# MTP10.net
KiCad netlist of a schematic drawn in Altium Designer
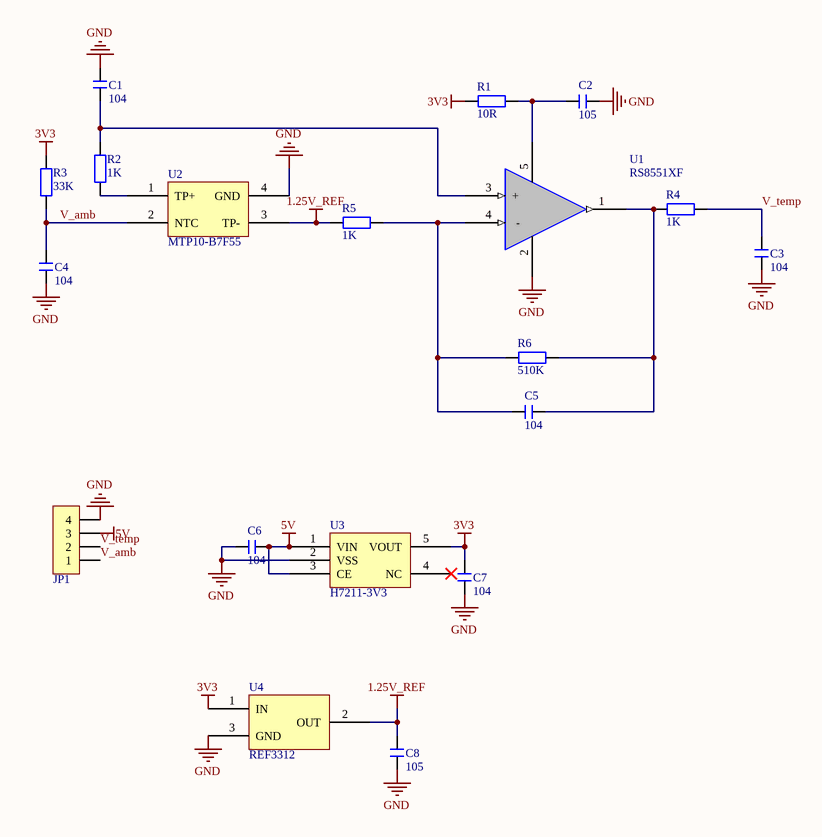
[diagram p0: MTP10.SchDoc]

(export (version "E")
  (design (tool "Eeschema 10.0.6"))
  (components
    (comp (ref "C1")
      (value "104")
      (footprint "C 0603_L")
      (description "无极性贴片电容")
      (fields (field (name "版权归属") "源创客"))
      (libsource (lib "3.1   - 电阻-电容-电感") (part "C"))
    )
    (comp (ref "C2")
      (value "105")
      (footprint "C 0603_L")
      (description "无极性贴片电容")
      (fields (field (name "版权归属") "源创客"))
      (libsource (lib "3.1   - 电阻-电容-电感") (part "C"))
    )
    (comp (ref "C3")
      (value "104")
      (footprint "C 0603_L")
      (description "无极性贴片电容")
      (fields (field (name "版权归属") "源创客"))
      (libsource (lib "3.1   - 电阻-电容-电感") (part "C"))
    )
    (comp (ref "C4")
      (value "104")
      (footprint "C 0603_L")
      (description "无极性贴片电容")
      (fields (field (name "版权归属") "源创客"))
      (libsource (lib "3.1   - 电阻-电容-电感") (part "C"))
    )
    (comp (ref "C5")
      (value "104")
      (footprint "C 0603_L")
      (description "无极性贴片电容")
      (fields (field (name "版权归属") "源创客"))
      (libsource (lib "3.1   - 电阻-电容-电感") (part "C"))
    )
    (comp (ref "C6")
      (value "104")
      (footprint "C 0603_L")
      (description "无极性贴片电容")
      (fields (field (name "版权归属") "源创客"))
      (libsource (lib "3.1   - 电阻-电容-电感") (part "C"))
    )
    (comp (ref "C7")
      (value "104")
      (footprint "C 0603_L")
      (description "无极性贴片电容")
      (fields (field (name "版权归属") "源创客"))
      (libsource (lib "3.1   - 电阻-电容-电感") (part "C"))
    )
    (comp (ref "C8")
      (value "105")
      (footprint "C 0603_L")
      (description "无极性贴片电容")
      (fields (field (name "版权归属") "源创客"))
      (libsource (lib "3.1   - 电阻-电容-电感") (part "C"))
    )
    (comp (ref "JP1")
      (value "HDR-1X4")
      (footprint "HDR2.54-LI-4P")
      (description "4P接插件")
      (fields (field (name "版权归属") "源创客"))
      (libsource (lib "4.5   - 接插件-脚距2.54") (part "Header 4"))
    )
    (comp (ref "R1")
      (value "10R")
      (footprint "R 0603_L")
      (description "贴片电阻")
      (fields (field (name "版权归属") "源创客"))
      (libsource (lib "3.1   - 电阻-电容-电感") (part "R"))
    )
    (comp (ref "R2")
      (value "1K")
      (footprint "R 0603_L")
      (description "贴片电阻")
      (fields (field (name "版权归属") "源创客"))
      (libsource (lib "3.1   - 电阻-电容-电感") (part "R"))
    )
    (comp (ref "R3")
      (value "33K")
      (footprint "R 0603_L")
      (description "贴片电阻")
      (fields (field (name "版权归属") "源创客"))
      (libsource (lib "3.1   - 电阻-电容-电感") (part "R"))
    )
    (comp (ref "R4")
      (value "1K")
      (footprint "R 0603_L")
      (description "贴片电阻")
      (fields (field (name "版权归属") "源创客"))
      (libsource (lib "3.1   - 电阻-电容-电感") (part "R"))
    )
    (comp (ref "R5")
      (value "1K")
      (footprint "R 0603_L")
      (description "贴片电阻")
      (fields (field (name "版权归属") "源创客"))
      (libsource (lib "3.1   - 电阻-电容-电感") (part "R"))
    )
    (comp (ref "R6")
      (value "510K")
      (footprint "R 0603_L")
      (description "贴片电阻")
      (fields (field (name "版权归属") "源创客"))
      (libsource (lib "3.1   - 电阻-电容-电感") (part "R"))
    )
    (comp (ref "U1")
      (value "RS8551XF")
      (footprint "SOT23-5M")
      (description "仪表放大器")
      (libsource (lib "MTP10") (part "RS8551XF"))
    )
    (comp (ref "U2")
      (value "MTP10-B7F55")
      (footprint "MTP-10B")
      (description "MEMS 热电堆芯片")
      (libsource (lib "MTP10") (part "MTP10-B7F55"))
    )
    (comp (ref "U3")
      (value "H7211-3V3")
      (footprint "SOT23-5")
      (description "低噪声LDO")
      (libsource (lib "LMT70") (part "H7211"))
    )
    (comp (ref "U4")
      (value "REF3312")
      (footprint "SOT23-3L")
      (description "电压基准")
      (libsource (lib "MTP10") (part "REF33XX"))
    )
  )
  (nets
    (net (code "1") (name "/V_amb") (class "Default")
      (node (ref "C4") (pin "2") (pinfunction "2_2") (pintype "passive"))
      (node (ref "JP1") (pin "1") (pinfunction "1_1") (pintype "passive"))
      (node (ref "R3") (pin "1") (pinfunction "1_1") (pintype "passive"))
      (node (ref "U2") (pin "2") (pinfunction "NTC_2") (pintype "passive"))
    )
    (net (code "2") (name "/V_temp") (class "Default")
      (node (ref "C3") (pin "2") (pinfunction "2_2") (pintype "passive"))
      (node (ref "JP1") (pin "2") (pinfunction "2_2") (pintype "passive"))
      (node (ref "R4") (pin "1") (pinfunction "1_1") (pintype "passive"))
    )
    (net (code "3") (name "1.25V_REF") (class "Default")
      (node (ref "C8") (pin "2") (pinfunction "2_2") (pintype "passive"))
      (node (ref "R5") (pin "2") (pinfunction "2_2") (pintype "passive"))
      (node (ref "U2") (pin "3") (pinfunction "TP-_3") (pintype "passive"))
      (node (ref "U4") (pin "2") (pinfunction "OUT_2") (pintype "passive"))
    )
    (net (code "4") (name "3V3") (class "Default")
      (node (ref "C7") (pin "2") (pinfunction "2_2") (pintype "passive"))
      (node (ref "R1") (pin "2") (pinfunction "2_2") (pintype "passive"))
      (node (ref "R3") (pin "2") (pinfunction "2_2") (pintype "passive"))
      (node (ref "U3") (pin "5") (pinfunction "VOUT_5") (pintype "passive"))
      (node (ref "U4") (pin "1") (pinfunction "IN_1") (pintype "passive"))
    )
    (net (code "5") (name "5V") (class "Default")
      (node (ref "C6") (pin "1") (pinfunction "1_1") (pintype "passive"))
      (node (ref "JP1") (pin "3") (pinfunction "3_3") (pintype "passive"))
      (node (ref "U3") (pin "1") (pinfunction "VIN_1") (pintype "passive"))
      (node (ref "U3") (pin "3") (pinfunction "CE_3") (pintype "passive"))
    )
    (net (code "6") (name "GND") (class "Default")
      (node (ref "C1") (pin "1") (pinfunction "1_1") (pintype "passive"))
      (node (ref "C2") (pin "2") (pinfunction "2_2") (pintype "passive"))
      (node (ref "C3") (pin "1") (pinfunction "1_1") (pintype "passive"))
      (node (ref "C4") (pin "1") (pinfunction "1_1") (pintype "passive"))
      (node (ref "C6") (pin "2") (pinfunction "2_2") (pintype "passive"))
      (node (ref "C7") (pin "1") (pinfunction "1_1") (pintype "passive"))
      (node (ref "C8") (pin "1") (pinfunction "1_1") (pintype "passive"))
      (node (ref "JP1") (pin "4") (pinfunction "4_4") (pintype "passive"))
      (node (ref "U1") (pin "2") (pinfunction "GND_2") (pintype "power_in"))
      (node (ref "U2") (pin "4") (pinfunction "GND_4") (pintype "passive"))
      (node (ref "U3") (pin "2") (pinfunction "VSS_2") (pintype "passive"))
      (node (ref "U4") (pin "3") (pinfunction "GND_3") (pintype "passive"))
    )
    (net (code "7") (name "Net-(U1-+)") (class "Default")
      (node (ref "C1") (pin "2") (pinfunction "2_2") (pintype "passive"))
      (node (ref "R2") (pin "2") (pinfunction "2_2") (pintype "passive"))
      (node (ref "U1") (pin "3") (pinfunction "+_3") (pintype "input"))
    )
    (net (code "8") (name "Net-(U1-OUT)") (class "Default")
      (node (ref "C5") (pin "2") (pinfunction "2_2") (pintype "passive"))
      (node (ref "R4") (pin "2") (pinfunction "2_2") (pintype "passive"))
      (node (ref "R6") (pin "1") (pinfunction "1_1") (pintype "passive"))
      (node (ref "U1") (pin "1") (pinfunction "OUT_1") (pintype "output"))
    )
    (net (code "9") (name "Net-(U1-VDD)") (class "Default")
      (node (ref "C2") (pin "1") (pinfunction "1_1") (pintype "passive"))
      (node (ref "R1") (pin "1") (pinfunction "1_1") (pintype "passive"))
      (node (ref "U1") (pin "5") (pinfunction "VDD_5") (pintype "power_in"))
    )
    (net (code "10") (name "Net-(U1-－)") (class "Default")
      (node (ref "C5") (pin "1") (pinfunction "1_1") (pintype "passive"))
      (node (ref "R5") (pin "1") (pinfunction "1_1") (pintype "passive"))
      (node (ref "R6") (pin "2") (pinfunction "2_2") (pintype "passive"))
      (node (ref "U1") (pin "4") (pinfunction "－_4") (pintype "input"))
    )
    (net (code "11") (name "Net-(U2-TP+)") (class "Default")
      (node (ref "R2") (pin "1") (pinfunction "1_1") (pintype "passive"))
      (node (ref "U2") (pin "1") (pinfunction "TP+_1") (pintype "passive"))
    )
    (net (code "12") (name "unconnected-(U3-NC-Pad4)") (class "Default")
      (node (ref "U3") (pin "4") (pinfunction "NC_4") (pintype "passive+no_connect"))
    )
  )
)
